# amp.net
KiCad netlist of a schematic drawn in EAGLE
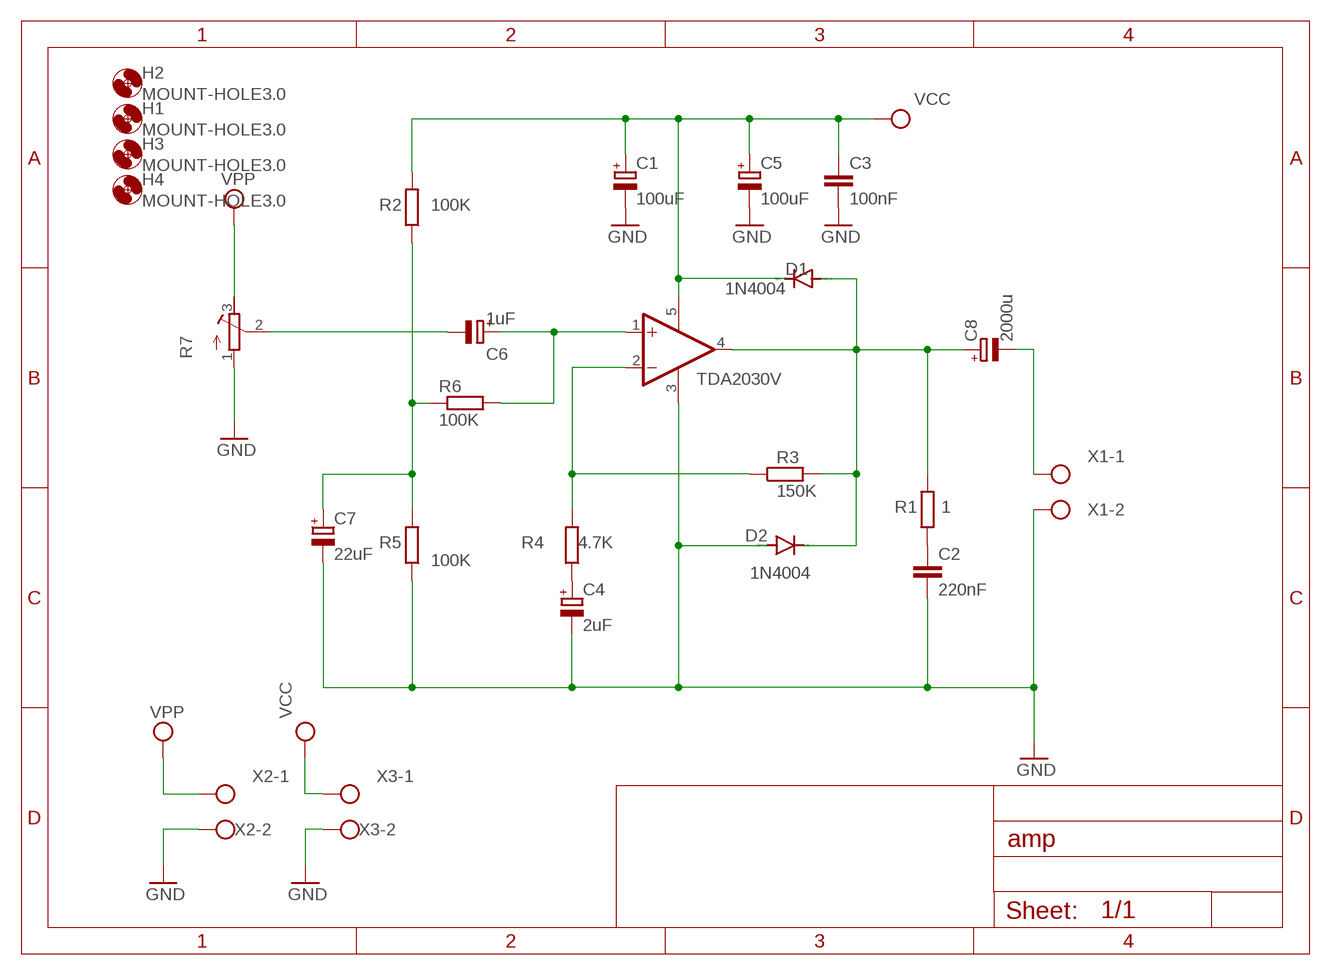
[diagram p0: schematic, sheet 1]

(export (version "E")
  (design (tool "Eeschema 10.0.6"))
  (components
    (comp (ref "C1")
      (value "100uF")
      (footprint "eagle-import:EB25D")
      (libsource (lib "eagle-import") (part "CPOL-EUE10-25"))
    )
    (comp (ref "C2")
      (value "220nF")
      (footprint "eagle-import:C2.5-3")
      (libsource (lib "eagle-import") (part "C2,5-3"))
    )
    (comp (ref "C3")
      (value "100nF")
      (footprint "eagle-import:C2.5-3")
      (libsource (lib "eagle-import") (part "C2,5-3"))
    )
    (comp (ref "C4")
      (value "2uF")
      (footprint "eagle-import:E2,5-7")
      (libsource (lib "eagle-import") (part "CPOL-EUE2.5-7"))
    )
    (comp (ref "C5")
      (value "100uF")
      (footprint "eagle-import:EB25D")
      (libsource (lib "eagle-import") (part "CPOL-EUE10-25"))
    )
    (comp (ref "C6")
      (value "1uF")
      (footprint "eagle-import:E2,5-7")
      (libsource (lib "eagle-import") (part "CPOL-EUE2.5-7"))
    )
    (comp (ref "C7")
      (value "22uF")
      (footprint "eagle-import:E2,5-7")
      (libsource (lib "eagle-import") (part "CPOL-EUE2.5-7"))
    )
    (comp (ref "C8")
      (value "2000u")
      (footprint "eagle-import:EB35D")
      (libsource (lib "eagle-import") (part "CPOL-EUE10-35"))
    )
    (comp (ref "D1")
      (value "1N4004")
      (footprint "eagle-import:DO41-10")
      (libsource (lib "eagle-import") (part "1N4004"))
    )
    (comp (ref "D2")
      (value "1N4004")
      (footprint "eagle-import:DO41-10")
      (libsource (lib "eagle-import") (part "1N4004"))
    )
    (comp (ref "H1")
      (value "MOUNT-HOLE3.0")
      (footprint "eagle-import:3,0")
      (libsource (lib "eagle-import") (part "MOUNT-HOLE3.0"))
    )
    (comp (ref "H2")
      (value "MOUNT-HOLE3.0")
      (footprint "eagle-import:3,0")
      (libsource (lib "eagle-import") (part "MOUNT-HOLE3.0"))
    )
    (comp (ref "H3")
      (value "MOUNT-HOLE3.0")
      (footprint "eagle-import:3,0")
      (libsource (lib "eagle-import") (part "MOUNT-HOLE3.0"))
    )
    (comp (ref "H4")
      (value "MOUNT-HOLE3.0")
      (footprint "eagle-import:3,0")
      (libsource (lib "eagle-import") (part "MOUNT-HOLE3.0"))
    )
    (comp (ref "IC1")
      (value "TDA2030V")
      (footprint "eagle-import:CB360")
      (libsource (lib "eagle-import") (part "TDA2030V"))
    )
    (comp (ref "R1")
      (value "1")
      (footprint "eagle-import:0207_12")
      (libsource (lib "eagle-import") (part "R-EU_0207/12"))
    )
    (comp (ref "R2")
      (value "100K")
      (footprint "eagle-import:0207_12")
      (libsource (lib "eagle-import") (part "R-EU_0207/12"))
    )
    (comp (ref "R3")
      (value "150K")
      (footprint "eagle-import:0207_12")
      (libsource (lib "eagle-import") (part "R-EU_0207/12"))
    )
    (comp (ref "R4")
      (value "4.7K")
      (footprint "eagle-import:0207_12")
      (libsource (lib "eagle-import") (part "R-EU_0207/12"))
    )
    (comp (ref "R5")
      (value "100K")
      (footprint "eagle-import:0207_12")
      (libsource (lib "eagle-import") (part "R-EU_0207/12"))
    )
    (comp (ref "R6")
      (value "100K")
      (footprint "eagle-import:0207_12")
      (libsource (lib "eagle-import") (part "R-EU_0207/12"))
    )
    (comp (ref "R7")
      (value "R-TRIMM3296W")
      (footprint "eagle-import:RTRIM3296W")
      (libsource (lib "eagle-import") (part "R-TRIMM3296W"))
    )
    (comp (ref "X1")
      (value "W237-113")
      (footprint "eagle-import:W237-113")
      (libsource (lib "eagle-import") (part "W237-113"))
    )
    (comp (ref "X2")
      (value "W237-113")
      (footprint "eagle-import:W237-113")
      (libsource (lib "eagle-import") (part "W237-113"))
    )
    (comp (ref "X3")
      (value "W237-113")
      (footprint "eagle-import:W237-113")
      (libsource (lib "eagle-import") (part "W237-113"))
    )
  )
  (nets
    (net (code "1") (name "GND") (class "Default")
      (node (ref "C1") (pin "-") (pinfunction "-_-") (pintype "passive"))
      (node (ref "C2") (pin "2") (pinfunction "2_2") (pintype "passive"))
      (node (ref "C3") (pin "2") (pinfunction "2_2") (pintype "passive"))
      (node (ref "C4") (pin "-") (pinfunction "-_-") (pintype "passive"))
      (node (ref "C5") (pin "-") (pinfunction "-_-") (pintype "passive"))
      (node (ref "C7") (pin "-") (pinfunction "-_-") (pintype "passive"))
      (node (ref "D2") (pin "A") (pinfunction "A_A") (pintype "passive"))
      (node (ref "IC1") (pin "3") (pinfunction "GND_3") (pintype "power_in"))
      (node (ref "R5") (pin "1") (pinfunction "1_1") (pintype "passive"))
      (node (ref "R7") (pin "1") (pinfunction "A_1") (pintype "passive"))
      (node (ref "X1") (pin "2") (pinfunction "KL_2") (pintype "passive"))
      (node (ref "X2") (pin "2") (pinfunction "KL_2") (pintype "passive"))
      (node (ref "X3") (pin "2") (pinfunction "KL_2") (pintype "passive"))
    )
    (net (code "2") (name "Net-(C2-Pad1)") (class "Default")
      (node (ref "C2") (pin "1") (pinfunction "1_1") (pintype "passive"))
      (node (ref "R1") (pin "1") (pinfunction "1_1") (pintype "passive"))
    )
    (net (code "3") (name "Net-(C4-Pad+)") (class "Default")
      (node (ref "C4") (pin "+") (pinfunction "+_+") (pintype "passive"))
      (node (ref "R4") (pin "1") (pinfunction "1_1") (pintype "passive"))
    )
    (net (code "4") (name "Net-(C7-Pad+)") (class "Default")
      (node (ref "C7") (pin "+") (pinfunction "+_+") (pintype "passive"))
      (node (ref "R2") (pin "1") (pinfunction "1_1") (pintype "passive"))
      (node (ref "R5") (pin "2") (pinfunction "2_2") (pintype "passive"))
      (node (ref "R6") (pin "1") (pinfunction "1_1") (pintype "passive"))
    )
    (net (code "5") (name "Net-(IC1-+IN)") (class "Default")
      (node (ref "C6") (pin "+") (pinfunction "+_+") (pintype "passive"))
      (node (ref "IC1") (pin "1") (pinfunction "+IN_1") (pintype "input"))
      (node (ref "R6") (pin "2") (pinfunction "2_2") (pintype "passive"))
    )
    (net (code "6") (name "Net-(IC1--IN)") (class "Default")
      (node (ref "IC1") (pin "2") (pinfunction "-IN_2") (pintype "input"))
      (node (ref "R3") (pin "1") (pinfunction "1_1") (pintype "passive"))
      (node (ref "R4") (pin "2") (pinfunction "2_2") (pintype "passive"))
    )
    (net (code "7") (name "Net-(IC1-OUT)") (class "Default")
      (node (ref "C8") (pin "+") (pinfunction "+_+") (pintype "passive"))
      (node (ref "D1") (pin "A") (pinfunction "A_A") (pintype "passive"))
      (node (ref "D2") (pin "C") (pinfunction "C_C") (pintype "passive"))
      (node (ref "IC1") (pin "4") (pinfunction "OUT_4") (pintype "output"))
      (node (ref "R1") (pin "2") (pinfunction "2_2") (pintype "passive"))
      (node (ref "R3") (pin "2") (pinfunction "2_2") (pintype "passive"))
    )
    (net (code "8") (name "Net-(R7-S)") (class "Default")
      (node (ref "C6") (pin "-") (pinfunction "-_-") (pintype "passive"))
      (node (ref "R7") (pin "2") (pinfunction "S_2") (pintype "passive"))
    )
    (net (code "9") (name "Net-(X1A-KL)") (class "Default")
      (node (ref "C8") (pin "-") (pinfunction "-_-") (pintype "passive"))
      (node (ref "X1") (pin "1") (pinfunction "KL_1") (pintype "passive"))
    )
    (net (code "10") (name "VCC") (class "Default")
      (node (ref "C1") (pin "+") (pinfunction "+_+") (pintype "passive"))
      (node (ref "C3") (pin "1") (pinfunction "1_1") (pintype "passive"))
      (node (ref "C5") (pin "+") (pinfunction "+_+") (pintype "passive"))
      (node (ref "D1") (pin "C") (pinfunction "C_C") (pintype "passive"))
      (node (ref "IC1") (pin "5") (pinfunction "V+_5") (pintype "power_in"))
      (node (ref "R2") (pin "2") (pinfunction "2_2") (pintype "passive"))
      (node (ref "X3") (pin "1") (pinfunction "KL_1") (pintype "passive"))
    )
    (net (code "11") (name "VPP") (class "Default")
      (node (ref "R7") (pin "3") (pinfunction "E_3") (pintype "passive"))
      (node (ref "X2") (pin "1") (pinfunction "KL_1") (pintype "passive"))
    )
  )
)
